# 07_-_CSI-DSI_RTC.net
KiCad netlist of a schematic drawn in Altium Designer
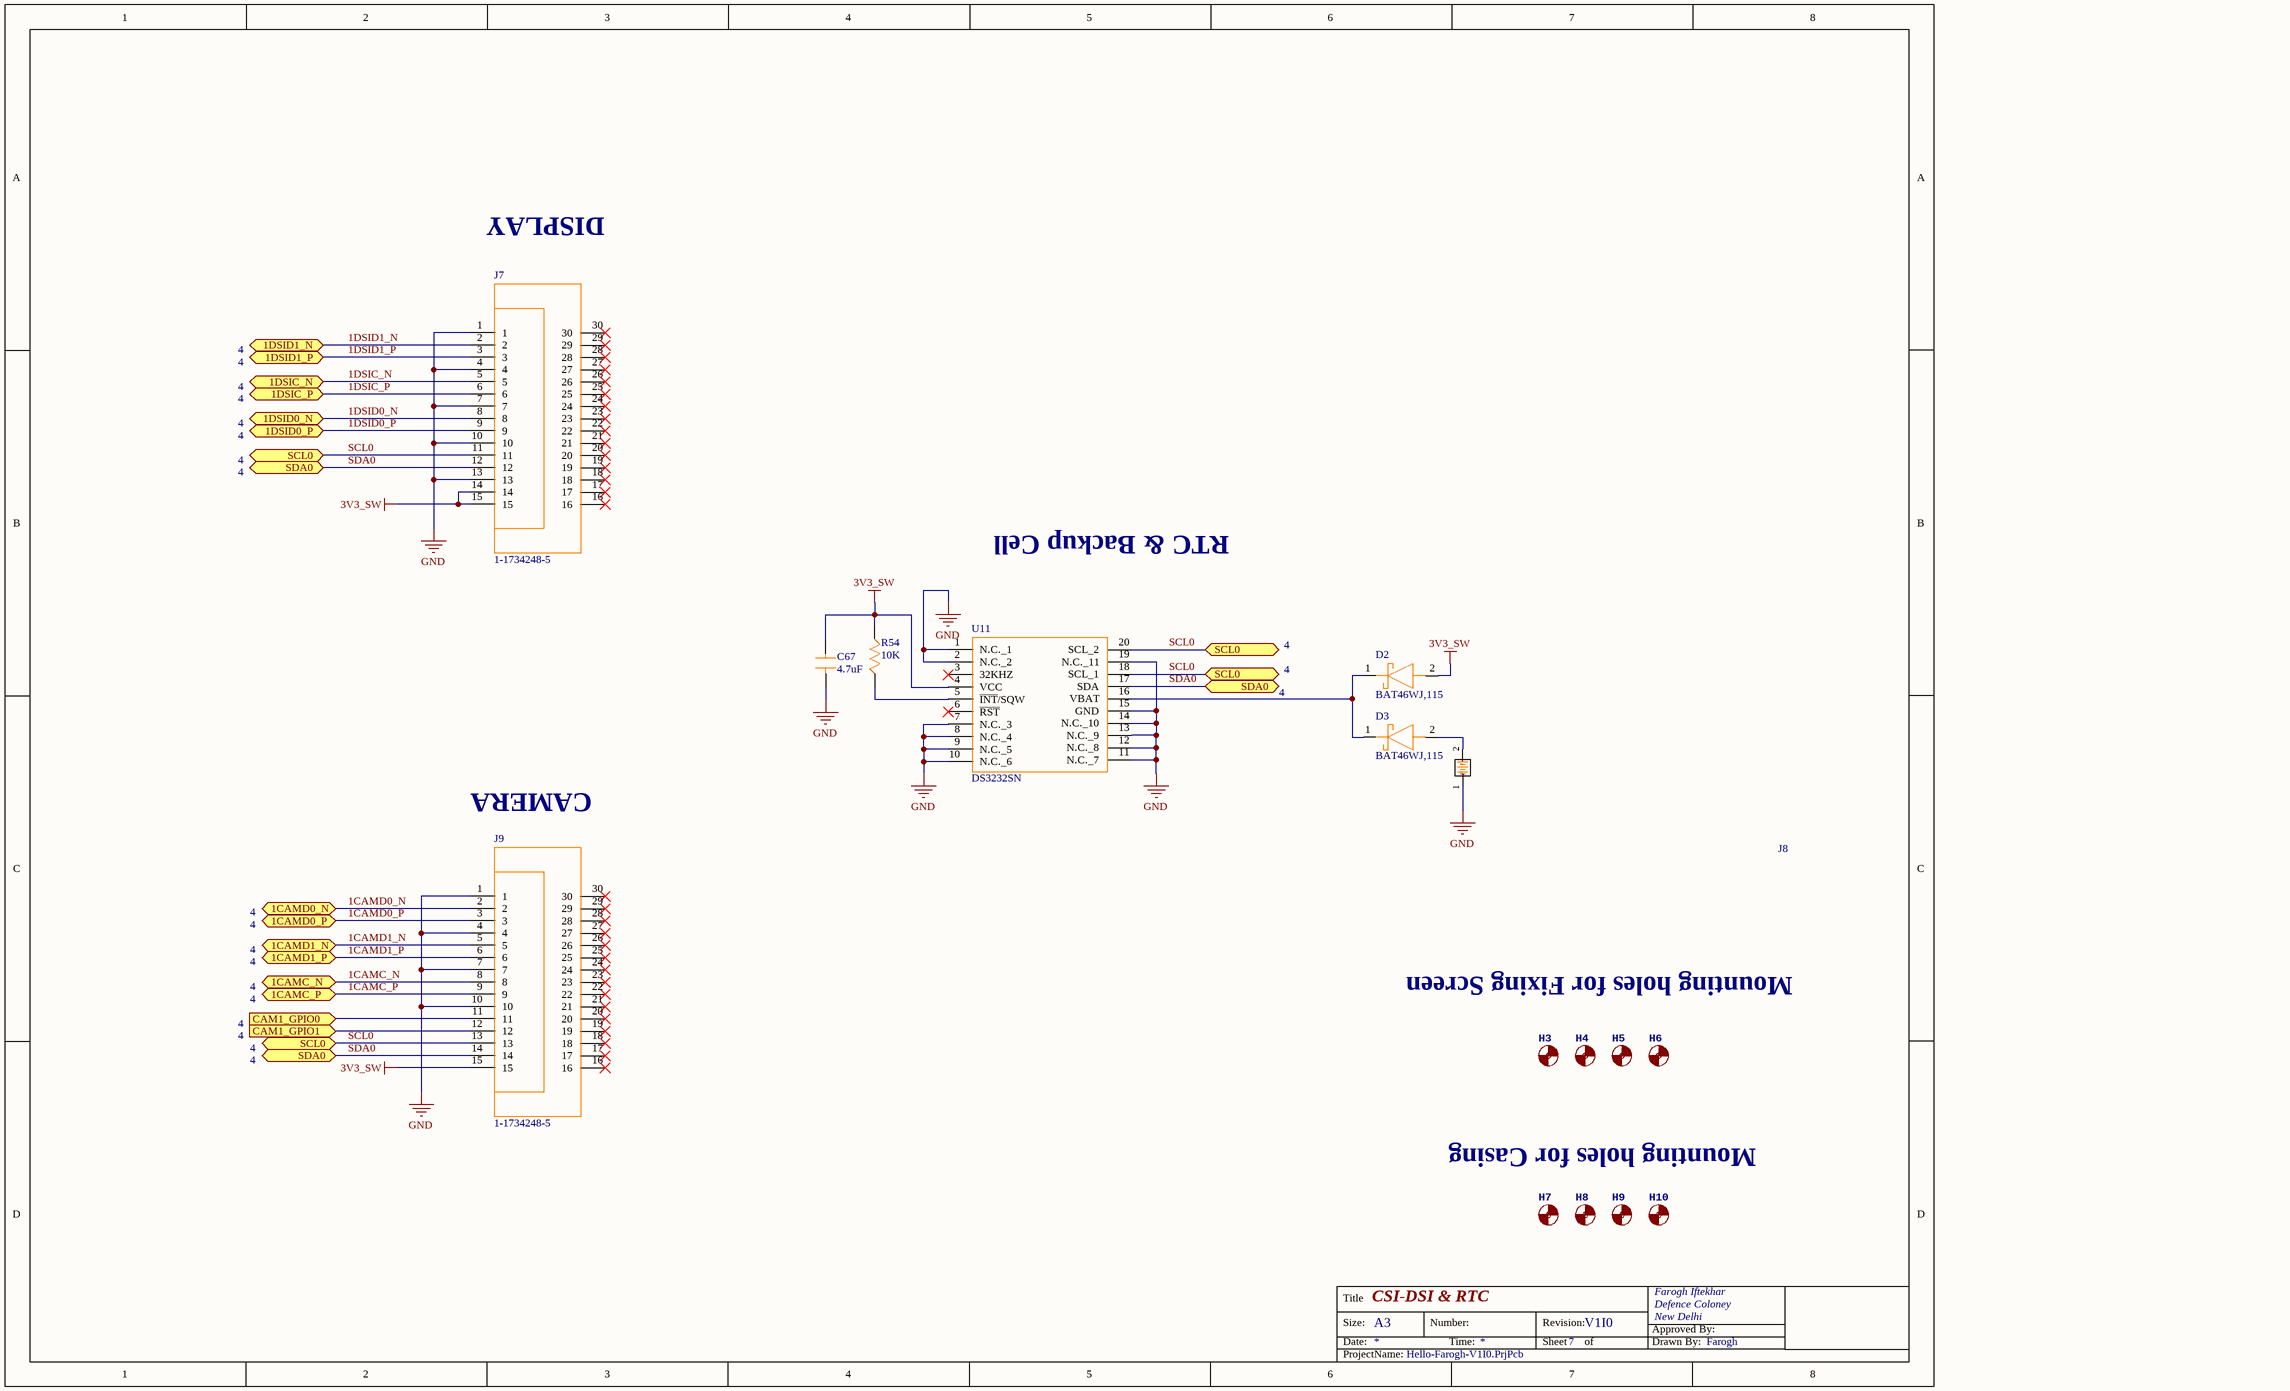
[diagram p0: [07] - CSI-DSI & RTC.SchDoc]

(export (version "E")
  (design (tool "Eeschema 10.0.6"))
  (components
    (comp (ref "C67")
      (value "4.7uF")
      (footprint "C0805")
      (description "Multilayer Ceramic Capacitors MLCC - SMD/SMT FACTORY NOT ACCEPTING ORDERS")
      (fields
        (field (name "MANUFACTURER") "KEMET")
        (field (name "MANUFACTURER PART NUMBER") "C0805X475K4RACAUTO")
      )
      (libsource (lib "Joule_Library") (part "C_0805-4.7uF"))
    )
    (comp (ref "D2")
      (value "BAT46WJ,115")
      (footprint "BAT46WJ,115")
      (description "Schottky Diodes & Rectifiers Schottky Diodes 100V 250mA Single")
      (fields (field (name "MANUFACTURER") "Nexperia"))
      (libsource (lib "Joule_Library") (part "BAT46WJ,115"))
    )
    (comp (ref "D3")
      (value "BAT46WJ,115")
      (footprint "BAT46WJ,115")
      (description "Schottky Diodes & Rectifiers Schottky Diodes 100V 250mA Single")
      (fields (field (name "MANUFACTURER") "Nexperia"))
      (libsource (lib "Joule_Library") (part "BAT46WJ,115"))
    )
    (comp (ref "H3")
      (value "MOUNTING HOLE with drill center marker")
      (footprint "3,0")
      (libsource (lib "holes") (part "MOUNT-HOLE3.0"))
    )
    (comp (ref "H4")
      (value "MOUNTING HOLE with drill center marker")
      (footprint "3,0")
      (libsource (lib "holes") (part "MOUNT-HOLE3.0"))
    )
    (comp (ref "H5")
      (value "MOUNTING HOLE with drill center marker")
      (footprint "3,0")
      (libsource (lib "holes") (part "MOUNT-HOLE3.0"))
    )
    (comp (ref "H6")
      (value "MOUNTING HOLE with drill center marker")
      (footprint "3,0")
      (libsource (lib "holes") (part "MOUNT-HOLE3.0"))
    )
    (comp (ref "H7")
      (value "MOUNTING HOLE with drill center marker")
      (footprint "3,0")
      (libsource (lib "holes") (part "MOUNT-HOLE3.0"))
    )
    (comp (ref "H8")
      (value "MOUNTING HOLE with drill center marker")
      (footprint "3,0")
      (libsource (lib "holes") (part "MOUNT-HOLE3.0"))
    )
    (comp (ref "H9")
      (value "MOUNTING HOLE with drill center marker")
      (footprint "3,0")
      (libsource (lib "holes") (part "MOUNT-HOLE3.0"))
    )
    (comp (ref "H10")
      (value "MOUNTING HOLE with drill center marker")
      (footprint "3,0")
      (libsource (lib "holes") (part "MOUNT-HOLE3.0"))
    )
    (comp (ref "J7")
      (value "1-1734248-5")
      (footprint "1-1734248-5")
      (description "FFC & FPC Connectors 15P 1.0 FPC, Zip V/T SMT")
      (fields (field (name "MANUFACTURER") "TE Connectivity / AMP"))
      (libsource (lib "Joule_Library") (part "CSI-1-1734248-5"))
    )
    (comp (ref "J8")
      (value "PRT-00783_F")
      (footprint "PRT-00783_F")
      (description "SparkFun Accessories Coin Cell Battery Holder - 20mm (PTH)")
      (fields (field (name "MANUFACTURER") "SparkFun") (field (name "MANUFACTURER PART NUMBER") "PRT-00783"))
      (libsource (lib "Joule_Library") (part "PRT-00783_F"))
    )
    (comp (ref "J9")
      (value "1-1734248-5")
      (footprint "1-1734248-5")
      (description "FFC & FPC Connectors 15P 1.0 FPC, Zip V/T SMT")
      (fields (field (name "MANUFACTURER") "TE Connectivity / AMP"))
      (libsource (lib "Joule_Library") (part "CSI-1-1734248-5"))
    )
    (comp (ref "R54")
      (value "10K")
      (footprint "R0805")
      (description "Thick Film Resistors - SMD 10K   OHM   1% 1/4W")
      (fields
        (field (name "MANUFACTURER") "Yageo")
        (field (name "MANUFACTURER PART NUMBER") "RC0805FR-7W10KL")
      )
      (libsource (lib "Joule_Library") (part "R_0805-10K"))
    )
    (comp (ref "U11")
      (value "DS3232SN")
      (footprint "DS3232SN")
      (description "Real Time Clock Integrated RTC/TCXO/Crystal")
      (fields
        (field (name "MANUFACTURER") "Maxim Integrated")
        (field (name "MANUFACTURER PART NUMBER") "DS3232SN#T&R")
      )
      (libsource (lib "Joule_Library") (part "DS3232SN"))
    )
  )
  (nets
    (net (code "1") (name "/1CAMC_N") (class "Default")
      (node (ref "J9") (pin "8") (pinfunction "8_8") (pintype "passive"))
    )
    (net (code "2") (name "/1CAMC_P") (class "Default")
      (node (ref "J9") (pin "9") (pinfunction "9_9") (pintype "passive"))
    )
    (net (code "3") (name "/1CAMD0_N") (class "Default")
      (node (ref "J9") (pin "2") (pinfunction "2_2") (pintype "passive"))
    )
    (net (code "4") (name "/1CAMD0_P") (class "Default")
      (node (ref "J9") (pin "3") (pinfunction "3_3") (pintype "passive"))
    )
    (net (code "5") (name "/1CAMD1_N") (class "Default")
      (node (ref "J9") (pin "5") (pinfunction "5_5") (pintype "passive"))
    )
    (net (code "6") (name "/1CAMD1_P") (class "Default")
      (node (ref "J9") (pin "6") (pinfunction "6_6") (pintype "passive"))
    )
    (net (code "7") (name "/1DSIC_N") (class "Default")
      (node (ref "J7") (pin "5") (pinfunction "5_5") (pintype "passive"))
    )
    (net (code "8") (name "/1DSIC_P") (class "Default")
      (node (ref "J7") (pin "6") (pinfunction "6_6") (pintype "passive"))
    )
    (net (code "9") (name "/1DSID0_N") (class "Default")
      (node (ref "J7") (pin "8") (pinfunction "8_8") (pintype "passive"))
    )
    (net (code "10") (name "/1DSID0_P") (class "Default")
      (node (ref "J7") (pin "9") (pinfunction "9_9") (pintype "passive"))
    )
    (net (code "11") (name "/1DSID1_N") (class "Default")
      (node (ref "J7") (pin "2") (pinfunction "2_2") (pintype "passive"))
    )
    (net (code "12") (name "/1DSID1_P") (class "Default")
      (node (ref "J7") (pin "3") (pinfunction "3_3") (pintype "passive"))
    )
    (net (code "13") (name "/CAM1_GPIO0") (class "Default")
      (node (ref "J9") (pin "11") (pinfunction "11_11") (pintype "passive"))
    )
    (net (code "14") (name "/CAM1_GPIO1") (class "Default")
      (node (ref "J9") (pin "12") (pinfunction "12_12") (pintype "passive"))
    )
    (net (code "15") (name "/SCL0") (class "Default")
      (node (ref "J7") (pin "11") (pinfunction "11_11") (pintype "passive"))
      (node (ref "J9") (pin "13") (pinfunction "13_13") (pintype "passive"))
      (node (ref "U11") (pin "18") (pinfunction "SCL_1_18") (pintype "passive"))
      (node (ref "U11") (pin "20") (pinfunction "SCL_2_20") (pintype "passive"))
    )
    (net (code "16") (name "/SDA0") (class "Default")
      (node (ref "J7") (pin "12") (pinfunction "12_12") (pintype "passive"))
      (node (ref "J9") (pin "14") (pinfunction "14_14") (pintype "passive"))
      (node (ref "U11") (pin "17") (pinfunction "SDA_17") (pintype "passive"))
    )
    (net (code "17") (name "3V3_SW") (class "Default")
      (node (ref "C67") (pin "2") (pinfunction "2_2") (pintype "passive"))
      (node (ref "D2") (pin "2") (pinfunction "A_2") (pintype "passive"))
      (node (ref "J7") (pin "14") (pinfunction "14_14") (pintype "passive"))
      (node (ref "J7") (pin "15") (pinfunction "15_15") (pintype "passive"))
      (node (ref "J9") (pin "15") (pinfunction "15_15") (pintype "passive"))
      (node (ref "R54") (pin "2") (pinfunction "2_2") (pintype "passive"))
      (node (ref "U11") (pin "4") (pinfunction "VCC_4") (pintype "passive"))
    )
    (net (code "18") (name "GND") (class "Default")
      (node (ref "C67") (pin "1") (pinfunction "1_1") (pintype "passive"))
      (node (ref "J7") (pin "1") (pinfunction "1_1") (pintype "passive"))
      (node (ref "J7") (pin "10") (pinfunction "10_10") (pintype "passive"))
      (node (ref "J7") (pin "13") (pinfunction "13_13") (pintype "passive"))
      (node (ref "J7") (pin "4") (pinfunction "4_4") (pintype "passive"))
      (node (ref "J7") (pin "7") (pinfunction "7_7") (pintype "passive"))
      (node (ref "J8") (pin "1") (pinfunction "-_1") (pintype "passive"))
      (node (ref "J9") (pin "1") (pinfunction "1_1") (pintype "passive"))
      (node (ref "J9") (pin "10") (pinfunction "10_10") (pintype "passive"))
      (node (ref "J9") (pin "4") (pinfunction "4_4") (pintype "passive"))
      (node (ref "J9") (pin "7") (pinfunction "7_7") (pintype "passive"))
      (node (ref "U11") (pin "1") (pinfunction "N.C._1_1") (pintype "passive"))
      (node (ref "U11") (pin "10") (pinfunction "N.C._6_10") (pintype "passive"))
      (node (ref "U11") (pin "11") (pinfunction "N.C._7_11") (pintype "passive"))
      (node (ref "U11") (pin "12") (pinfunction "N.C._8_12") (pintype "passive"))
      (node (ref "U11") (pin "13") (pinfunction "N.C._9_13") (pintype "passive"))
      (node (ref "U11") (pin "14") (pinfunction "N.C._10_14") (pintype "passive"))
      (node (ref "U11") (pin "15") (pinfunction "GND_15") (pintype "passive"))
      (node (ref "U11") (pin "19") (pinfunction "N.C._11_19") (pintype "passive"))
      (node (ref "U11") (pin "2") (pinfunction "N.C._2_2") (pintype "passive"))
      (node (ref "U11") (pin "7") (pinfunction "N.C._3_7") (pintype "passive"))
      (node (ref "U11") (pin "8") (pinfunction "N.C._4_8") (pintype "passive"))
      (node (ref "U11") (pin "9") (pinfunction "N.C._5_9") (pintype "passive"))
    )
    (net (code "19") (name "Net-(D2-K)") (class "Default")
      (node (ref "D2") (pin "1") (pinfunction "K_1") (pintype "passive"))
      (node (ref "D3") (pin "1") (pinfunction "K_1") (pintype "passive"))
      (node (ref "U11") (pin "16") (pinfunction "VBAT_16") (pintype "passive"))
    )
    (net (code "20") (name "Net-(D3-A)") (class "Default")
      (node (ref "D3") (pin "2") (pinfunction "A_2") (pintype "passive"))
      (node (ref "J8") (pin "2") (pinfunction "+_2") (pintype "passive"))
    )
    (net (code "21") (name "Net-(U11-~{INT}{slash}SQW)") (class "Default")
      (node (ref "R54") (pin "1") (pinfunction "1_1") (pintype "passive"))
      (node (ref "U11") (pin "5") (pinfunction "~{INT}/SQW_5") (pintype "passive"))
    )
    (net (code "22") (name "unconnected-(J7-Pad16)") (class "Default")
      (node (ref "J7") (pin "16") (pinfunction "16_16") (pintype "passive+no_connect"))
    )
    (net (code "23") (name "unconnected-(J7-Pad17)") (class "Default")
      (node (ref "J7") (pin "17") (pinfunction "17_17") (pintype "passive+no_connect"))
    )
    (net (code "24") (name "unconnected-(J7-Pad18)") (class "Default")
      (node (ref "J7") (pin "18") (pinfunction "18_18") (pintype "passive+no_connect"))
    )
    (net (code "25") (name "unconnected-(J7-Pad19)") (class "Default")
      (node (ref "J7") (pin "19") (pinfunction "19_19") (pintype "passive+no_connect"))
    )
    (net (code "26") (name "unconnected-(J7-Pad20)") (class "Default")
      (node (ref "J7") (pin "20") (pinfunction "20_20") (pintype "passive+no_connect"))
    )
    (net (code "27") (name "unconnected-(J7-Pad21)") (class "Default")
      (node (ref "J7") (pin "21") (pinfunction "21_21") (pintype "passive+no_connect"))
    )
    (net (code "28") (name "unconnected-(J7-Pad22)") (class "Default")
      (node (ref "J7") (pin "22") (pinfunction "22_22") (pintype "passive+no_connect"))
    )
    (net (code "29") (name "unconnected-(J7-Pad23)") (class "Default")
      (node (ref "J7") (pin "23") (pinfunction "23_23") (pintype "passive+no_connect"))
    )
    (net (code "30") (name "unconnected-(J7-Pad24)") (class "Default")
      (node (ref "J7") (pin "24") (pinfunction "24_24") (pintype "passive+no_connect"))
    )
    (net (code "31") (name "unconnected-(J7-Pad25)") (class "Default")
      (node (ref "J7") (pin "25") (pinfunction "25_25") (pintype "passive+no_connect"))
    )
    (net (code "32") (name "unconnected-(J7-Pad26)") (class "Default")
      (node (ref "J7") (pin "26") (pinfunction "26_26") (pintype "passive+no_connect"))
    )
    (net (code "33") (name "unconnected-(J7-Pad27)") (class "Default")
      (node (ref "J7") (pin "27") (pinfunction "27_27") (pintype "passive+no_connect"))
    )
    (net (code "34") (name "unconnected-(J7-Pad28)") (class "Default")
      (node (ref "J7") (pin "28") (pinfunction "28_28") (pintype "passive+no_connect"))
    )
    (net (code "35") (name "unconnected-(J7-Pad29)") (class "Default")
      (node (ref "J7") (pin "29") (pinfunction "29_29") (pintype "passive+no_connect"))
    )
    (net (code "36") (name "unconnected-(J7-Pad30)") (class "Default")
      (node (ref "J7") (pin "30") (pinfunction "30_30") (pintype "passive+no_connect"))
    )
    (net (code "37") (name "unconnected-(J9-Pad16)") (class "Default")
      (node (ref "J9") (pin "16") (pinfunction "16_16") (pintype "passive+no_connect"))
    )
    (net (code "38") (name "unconnected-(J9-Pad17)") (class "Default")
      (node (ref "J9") (pin "17") (pinfunction "17_17") (pintype "passive+no_connect"))
    )
    (net (code "39") (name "unconnected-(J9-Pad18)") (class "Default")
      (node (ref "J9") (pin "18") (pinfunction "18_18") (pintype "passive+no_connect"))
    )
    (net (code "40") (name "unconnected-(J9-Pad19)") (class "Default")
      (node (ref "J9") (pin "19") (pinfunction "19_19") (pintype "passive+no_connect"))
    )
    (net (code "41") (name "unconnected-(J9-Pad20)") (class "Default")
      (node (ref "J9") (pin "20") (pinfunction "20_20") (pintype "passive+no_connect"))
    )
    (net (code "42") (name "unconnected-(J9-Pad21)") (class "Default")
      (node (ref "J9") (pin "21") (pinfunction "21_21") (pintype "passive+no_connect"))
    )
    (net (code "43") (name "unconnected-(J9-Pad22)") (class "Default")
      (node (ref "J9") (pin "22") (pinfunction "22_22") (pintype "passive+no_connect"))
    )
    (net (code "44") (name "unconnected-(J9-Pad23)") (class "Default")
      (node (ref "J9") (pin "23") (pinfunction "23_23") (pintype "passive+no_connect"))
    )
    (net (code "45") (name "unconnected-(J9-Pad24)") (class "Default")
      (node (ref "J9") (pin "24") (pinfunction "24_24") (pintype "passive+no_connect"))
    )
    (net (code "46") (name "unconnected-(J9-Pad25)") (class "Default")
      (node (ref "J9") (pin "25") (pinfunction "25_25") (pintype "passive+no_connect"))
    )
    (net (code "47") (name "unconnected-(J9-Pad26)") (class "Default")
      (node (ref "J9") (pin "26") (pinfunction "26_26") (pintype "passive+no_connect"))
    )
    (net (code "48") (name "unconnected-(J9-Pad27)") (class "Default")
      (node (ref "J9") (pin "27") (pinfunction "27_27") (pintype "passive+no_connect"))
    )
    (net (code "49") (name "unconnected-(J9-Pad28)") (class "Default")
      (node (ref "J9") (pin "28") (pinfunction "28_28") (pintype "passive+no_connect"))
    )
    (net (code "50") (name "unconnected-(J9-Pad29)") (class "Default")
      (node (ref "J9") (pin "29") (pinfunction "29_29") (pintype "passive+no_connect"))
    )
    (net (code "51") (name "unconnected-(J9-Pad30)") (class "Default")
      (node (ref "J9") (pin "30") (pinfunction "30_30") (pintype "passive+no_connect"))
    )
    (net (code "52") (name "unconnected-(U11-32KHZ-Pad3)") (class "Default")
      (node (ref "U11") (pin "3") (pinfunction "32KHZ_3") (pintype "passive+no_connect"))
    )
    (net (code "53") (name "unconnected-(U11-~{RST}-Pad6)") (class "Default")
      (node (ref "U11") (pin "6") (pinfunction "~{RST}_6") (pintype "passive+no_connect"))
    )
  )
)
